# 10_-MODEM_CONNECTORS.net
KiCad netlist of a schematic drawn in Altium Designer
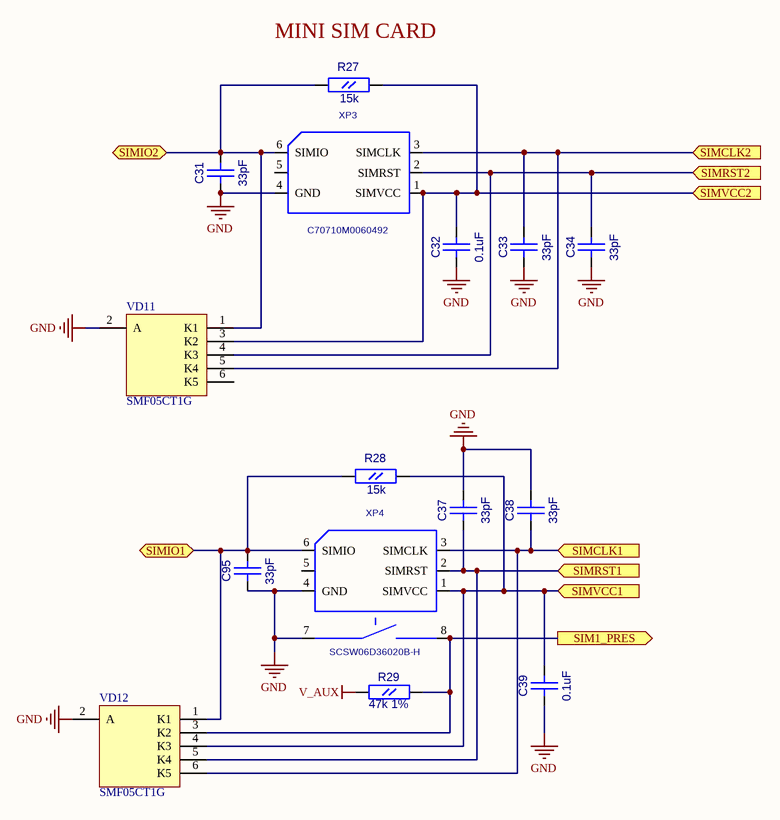
[diagram p0: [10]-MODEM_CONNECTORS.SchDoc]

(export (version "E")
  (design (tool "Eeschema 10.0.6"))
  (components
    (comp (ref "C31")
      (value "33pF")
      (footprint "CC0603")
      (description "CC0603")
      (libsource (lib "gprs_modem_2") (part "CC0603"))
    )
    (comp (ref "C32")
      (value "0.1uF")
      (footprint "CC0603")
      (description "CC0603")
      (libsource (lib "gprs_modem_2") (part "CC0603"))
    )
    (comp (ref "C33")
      (value "33pF")
      (footprint "CC0603")
      (description "CC0603")
      (libsource (lib "gprs_modem_2") (part "CC0603"))
    )
    (comp (ref "C34")
      (value "33pF")
      (footprint "CC0603")
      (description "CC0603")
      (libsource (lib "gprs_modem_2") (part "CC0603"))
    )
    (comp (ref "C37")
      (value "33pF")
      (footprint "CC0603")
      (description "CC0603")
      (libsource (lib "gprs_modem_2") (part "CC0603"))
    )
    (comp (ref "C38")
      (value "33pF")
      (footprint "CC0603")
      (description "CC0603")
      (libsource (lib "gprs_modem_2") (part "CC0603"))
    )
    (comp (ref "C39")
      (value "0.1uF")
      (footprint "CC0603")
      (description "CC0603")
      (libsource (lib "gprs_modem_2") (part "CC0603"))
    )
    (comp (ref "C95")
      (value "33pF")
      (footprint "CC0603")
      (description "CC0603")
      (libsource (lib "gprs_modem_2") (part "CC0603"))
    )
    (comp (ref "R27")
      (value "15k")
      (footprint "RC0603")
      (description "RC0603")
      (libsource (lib "fizik_lib (1)") (part "RC0603"))
    )
    (comp (ref "R28")
      (value "15k")
      (footprint "RC0603")
      (description "RC0603")
      (libsource (lib "fizik_lib (1)") (part "RC0603"))
    )
    (comp (ref "R29")
      (value "47k 1%")
      (footprint "RC0603")
      (description "RC0603")
      (libsource (lib "gprs_modem_2") (part "RC0603"))
    )
    (comp (ref "VD11")
      (value "SMF05CT1G")
      (footprint "SOT-363")
      (description "5-Line Transient Voltage Suppressor Array, 6-Pin SC70, Pb-Free, Tape and Reel")
      (fields (field (name "MANUFACTURER") "On Semiconductor"))
      (libsource (lib "gprs_modem_2") (part "SMF05CT1G"))
    )
    (comp (ref "VD12")
      (value "SMF05CT1G")
      (footprint "SOT-363")
      (description "5-Line Transient Voltage Suppressor Array, 6-Pin SC70, Pb-Free, Tape and Reel")
      (fields (field (name "MANUFACTURER") "On Semiconductor"))
      (libsource (lib "gprs_modem_2") (part "SMF05CT1G"))
    )
    (comp (ref "XP3")
      (value "C70710M0060492")
      (footprint "SCVW06A25020")
      (description "SCV-W06A25-020")
      (libsource (lib "gprs_modem_2") (part "SCV-W06A25-020"))
    )
    (comp (ref "XP4")
      (value "SCSW06D36020B-H")
      (footprint "SCSW06D36020B-H")
      (libsource (lib "fizik_lib (1)") (part "SCSW06D36020B-H"))
    )
  )
  (nets
    (net (code "1") (name "/SIM1_PRES") (class "Default")
      (node (ref "R29") (pin "2") (pinfunction "B_2") (pintype "passive"))
      (node (ref "VD12") (pin "3") (pinfunction "K2_3") (pintype "passive"))
      (node (ref "XP4") (pin "8") (pintype "passive"))
    )
    (net (code "2") (name "/SIMCLK1") (class "Default")
      (node (ref "C38") (pin "1") (pinfunction "A_1") (pintype "passive"))
      (node (ref "VD12") (pin "6") (pinfunction "K5_6") (pintype "passive"))
      (node (ref "XP4") (pin "3") (pinfunction "SIMCLK_3") (pintype "passive"))
    )
    (net (code "3") (name "/SIMCLK2") (class "Default")
      (node (ref "C33") (pin "2") (pinfunction "B_2") (pintype "passive"))
      (node (ref "VD11") (pin "5") (pinfunction "K4_5") (pintype "passive"))
      (node (ref "XP3") (pin "3") (pinfunction "SIMCLK_3") (pintype "passive"))
    )
    (net (code "4") (name "/SIMIO1") (class "Default")
      (node (ref "C95") (pin "2") (pinfunction "B_2") (pintype "passive"))
      (node (ref "R28") (pin "1") (pinfunction "A_1") (pintype "passive"))
      (node (ref "VD12") (pin "1") (pinfunction "K1_1") (pintype "passive"))
      (node (ref "XP4") (pin "6") (pinfunction "SIMIO_6") (pintype "passive"))
    )
    (net (code "5") (name "/SIMIO2") (class "Default")
      (node (ref "C31") (pin "2") (pinfunction "B_2") (pintype "passive"))
      (node (ref "R27") (pin "1") (pinfunction "A_1") (pintype "passive"))
      (node (ref "VD11") (pin "1") (pinfunction "K1_1") (pintype "passive"))
      (node (ref "XP3") (pin "6") (pinfunction "SIMIO_6") (pintype "passive"))
    )
    (net (code "6") (name "/SIMRST1") (class "Default")
      (node (ref "C37") (pin "1") (pinfunction "A_1") (pintype "passive"))
      (node (ref "VD12") (pin "5") (pinfunction "K4_5") (pintype "passive"))
      (node (ref "XP4") (pin "2") (pinfunction "SIMRST_2") (pintype "passive"))
    )
    (net (code "7") (name "/SIMRST2") (class "Default")
      (node (ref "C34") (pin "2") (pinfunction "B_2") (pintype "passive"))
      (node (ref "VD11") (pin "4") (pinfunction "K3_4") (pintype "passive"))
      (node (ref "XP3") (pin "2") (pinfunction "SIMRST_2") (pintype "passive"))
    )
    (net (code "8") (name "/SIMVCC1") (class "Default")
      (node (ref "C39") (pin "2") (pinfunction "B_2") (pintype "passive"))
      (node (ref "R28") (pin "2") (pinfunction "B_2") (pintype "passive"))
      (node (ref "VD12") (pin "4") (pinfunction "K3_4") (pintype "passive"))
      (node (ref "XP4") (pin "1") (pinfunction "SIMVCC_1") (pintype "passive"))
    )
    (net (code "9") (name "/SIMVCC2") (class "Default")
      (node (ref "C32") (pin "2") (pinfunction "B_2") (pintype "passive"))
      (node (ref "R27") (pin "2") (pinfunction "B_2") (pintype "passive"))
      (node (ref "VD11") (pin "3") (pinfunction "K2_3") (pintype "passive"))
      (node (ref "XP3") (pin "1") (pinfunction "SIMVCC_1") (pintype "passive"))
    )
    (net (code "10") (name "GND") (class "Default")
      (node (ref "C31") (pin "1") (pinfunction "A_1") (pintype "passive"))
      (node (ref "C32") (pin "1") (pinfunction "A_1") (pintype "passive"))
      (node (ref "C33") (pin "1") (pinfunction "A_1") (pintype "passive"))
      (node (ref "C34") (pin "1") (pinfunction "A_1") (pintype "passive"))
      (node (ref "C37") (pin "2") (pinfunction "B_2") (pintype "passive"))
      (node (ref "C38") (pin "2") (pinfunction "B_2") (pintype "passive"))
      (node (ref "C39") (pin "1") (pinfunction "A_1") (pintype "passive"))
      (node (ref "C95") (pin "1") (pinfunction "A_1") (pintype "passive"))
      (node (ref "VD11") (pin "2") (pinfunction "A_2") (pintype "passive"))
      (node (ref "VD12") (pin "2") (pinfunction "A_2") (pintype "passive"))
      (node (ref "XP3") (pin "4") (pinfunction "GND_4") (pintype "passive"))
      (node (ref "XP4") (pin "4") (pinfunction "GND_4") (pintype "passive"))
      (node (ref "XP4") (pin "7") (pintype "passive"))
    )
    (net (code "11") (name "V_AUX") (class "Default")
      (node (ref "R29") (pin "1") (pinfunction "A_1") (pintype "passive"))
    )
    (net (code "12") (name "unconnected-(VD11-K5-Pad6)") (class "Default")
      (node (ref "VD11") (pin "6") (pinfunction "K5_6") (pintype "passive"))
    )
    (net (code "13") (name "unconnected-(XP3-Pad5)") (class "Default")
      (node (ref "XP3") (pin "5") (pintype "passive"))
    )
    (net (code "14") (name "unconnected-(XP4-Pad5)") (class "Default")
      (node (ref "XP4") (pin "5") (pintype "passive"))
    )
  )
)
